# FLC100_remote_HV_v1.net
KiCad netlist of a schematic drawn in EAGLE
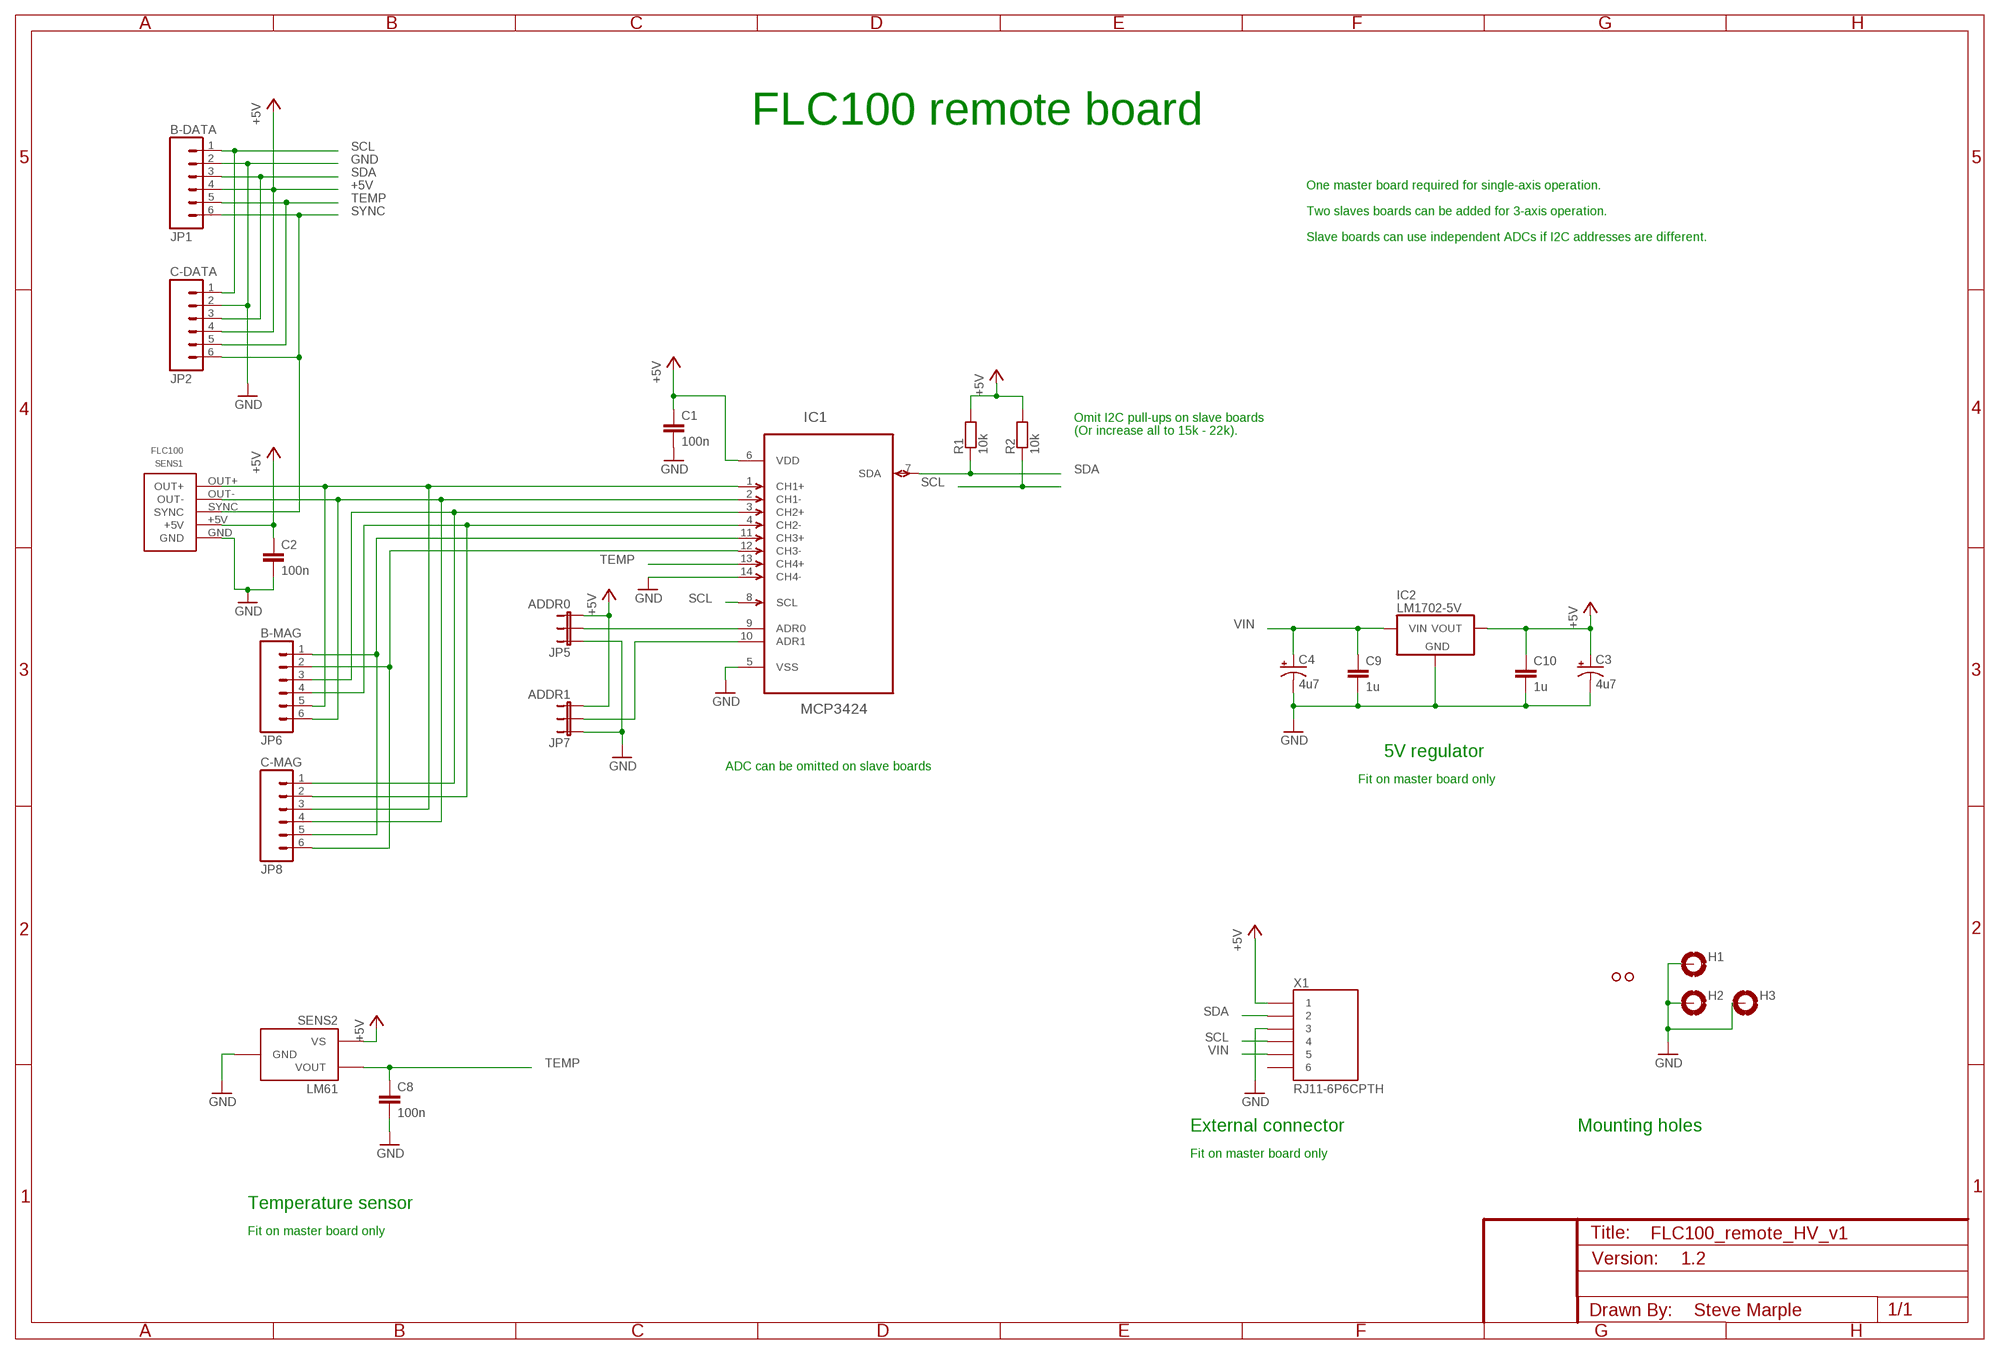
[diagram p0: schematic, sheet 1]

(export (version "E")
  (design (tool "Eeschema 10.0.6"))
  (components
    (comp (ref "C1")
      (value "100n")
      (footprint "eagle-import:CAP-PTH-SMALL")
      (libsource (lib "eagle-import") (part "CAPPTH"))
    )
    (comp (ref "C2")
      (value "100n")
      (footprint "eagle-import:CAP-PTH-SMALL")
      (libsource (lib "eagle-import") (part "CAPPTH"))
    )
    (comp (ref "C3")
      (value "4u7")
      (footprint "eagle-import:CPOL-RADIAL-10UF-25V")
      (libsource (lib "eagle-import") (part "CAP_POLPTH2"))
    )
    (comp (ref "C4")
      (value "4u7")
      (footprint "eagle-import:CPOL-RADIAL-10UF-25V")
      (libsource (lib "eagle-import") (part "CAP_POLPTH2"))
    )
    (comp (ref "C8")
      (value "100n")
      (footprint "eagle-import:CAP-PTH-SMALL")
      (libsource (lib "eagle-import") (part "CAPPTH"))
    )
    (comp (ref "C9")
      (value "1u")
      (footprint "eagle-import:CAP-PTH-5MM")
      (libsource (lib "eagle-import") (part "CAPPTH1"))
    )
    (comp (ref "C10")
      (value "1u")
      (footprint "eagle-import:CAP-PTH-5MM")
      (libsource (lib "eagle-import") (part "CAPPTH1"))
    )
    (comp (ref "H1")
      (value "MOUNT-PAD-ROUND3.0")
      (footprint "eagle-import:3,0-PAD")
      (libsource (lib "eagle-import") (part "MOUNT-PAD-ROUND3.0"))
    )
    (comp (ref "H2")
      (value "MOUNT-PAD-ROUND3.0")
      (footprint "eagle-import:3,0-PAD")
      (libsource (lib "eagle-import") (part "MOUNT-PAD-ROUND3.0"))
    )
    (comp (ref "H3")
      (value "MOUNT-PAD-ROUND3.0")
      (footprint "eagle-import:3,0-PAD")
      (libsource (lib "eagle-import") (part "MOUNT-PAD-ROUND3.0"))
    )
    (comp (ref "IC1")
      (value "MCP3424")
      (footprint "eagle-import:SO14-HAND")
      (libsource (lib "eagle-import") (part "MCP3424-E/SLSO14-HAND"))
    )
    (comp (ref "IC2")
      (value "LM1702-5V")
      (footprint "eagle-import:TO-92@2")
      (libsource (lib "eagle-import") (part "LM1702"))
    )
    (comp (ref "JP1")
      (value "B-DATA")
      (footprint "eagle-import:1X06_FEMALE")
      (libsource (lib "eagle-import") (part "M06FEMALE"))
    )
    (comp (ref "JP2")
      (value "C-DATA")
      (footprint "eagle-import:1X06_FEMALE")
      (libsource (lib "eagle-import") (part "M06FEMALE"))
    )
    (comp (ref "JP5")
      (value "ADDR0")
      (footprint "eagle-import:1X03")
      (libsource (lib "eagle-import") (part "JUMPER-3PTH"))
    )
    (comp (ref "JP6")
      (value "B-MAG")
      (footprint "eagle-import:1X06_FEMALE")
      (libsource (lib "eagle-import") (part "M06FEMALE"))
    )
    (comp (ref "JP7")
      (value "ADDR1")
      (footprint "eagle-import:1X03")
      (libsource (lib "eagle-import") (part "JUMPER-3PTH"))
    )
    (comp (ref "JP8")
      (value "C-MAG")
      (footprint "eagle-import:1X06_FEMALE")
      (libsource (lib "eagle-import") (part "M06FEMALE"))
    )
    (comp (ref "R1")
      (value "10k")
      (footprint "eagle-import:RES-AXIAL-0.4")
      (libsource (lib "eagle-import") (part "RESISTOR"))
    )
    (comp (ref "R2")
      (value "10k")
      (footprint "eagle-import:RES-AXIAL-0.4")
      (libsource (lib "eagle-import") (part "RESISTOR"))
    )
    (comp (ref "SENS1")
      (value "FLC100")
      (footprint "eagle-import:FLC100")
      (libsource (lib "eagle-import") (part "FLC100"))
    )
    (comp (ref "SENS2")
      (value "LM61")
      (footprint "eagle-import:TO-92")
      (libsource (lib "eagle-import") (part "LM61"))
    )
    (comp (ref "U$1")
      (value "PAD")
      (footprint "eagle-import:PAD")
      (libsource (lib "eagle-import") (part "PAD"))
    )
    (comp (ref "U$2")
      (value "PAD")
      (footprint "eagle-import:PAD")
      (libsource (lib "eagle-import") (part "PAD"))
    )
    (comp (ref "X1")
      (value "RJ11-6P6CPTH")
      (footprint "eagle-import:RJ11-6P6C")
      (libsource (lib "eagle-import") (part "RJ11-6P6CPTH"))
    )
  )
  (nets
    (net (code "1") (name "+5V") (class "Default")
      (node (ref "C1") (pin "1") (pinfunction "1_1") (pintype "passive"))
      (node (ref "C10") (pin "1") (pinfunction "1_1") (pintype "passive"))
      (node (ref "C2") (pin "1") (pinfunction "1_1") (pintype "passive"))
      (node (ref "C3") (pin "1") (pinfunction "+_1") (pintype "passive"))
      (node (ref "IC1") (pin "6") (pinfunction "VDD_6") (pintype "power_in"))
      (node (ref "IC2") (pin "3") (pinfunction "VOUT_3") (pintype "passive"))
      (node (ref "JP1") (pin "4") (pinfunction "4_4") (pintype "passive"))
      (node (ref "JP2") (pin "4") (pinfunction "4_4") (pintype "passive"))
      (node (ref "JP5") (pin "3") (pinfunction "3_3") (pintype "passive"))
      (node (ref "JP7") (pin "3") (pinfunction "3_3") (pintype "passive"))
      (node (ref "R1") (pin "P$2") (pinfunction "2_P$2") (pintype "passive"))
      (node (ref "R2") (pin "P$2") (pinfunction "2_P$2") (pintype "passive"))
      (node (ref "SENS1") (pin "+5V") (pinfunction "+5V_+5V") (pintype "power_in"))
      (node (ref "SENS2") (pin "1") (pinfunction "VS_1") (pintype "bidirectional"))
      (node (ref "X1") (pin "1") (pinfunction "1_1") (pintype "bidirectional"))
    )
    (net (code "2") (name "/SCL") (class "Default")
      (node (ref "IC1") (pin "8") (pinfunction "SCL_8") (pintype "input"))
      (node (ref "JP1") (pin "1") (pinfunction "1_1") (pintype "passive"))
      (node (ref "JP2") (pin "1") (pinfunction "1_1") (pintype "passive"))
      (node (ref "R2") (pin "P$1") (pinfunction "1_P$1") (pintype "passive"))
      (node (ref "X1") (pin "4") (pinfunction "4_4") (pintype "bidirectional"))
    )
    (net (code "3") (name "/SDA") (class "Default")
      (node (ref "IC1") (pin "7") (pinfunction "SDA_7") (pintype "bidirectional"))
      (node (ref "JP1") (pin "3") (pinfunction "3_3") (pintype "passive"))
      (node (ref "JP2") (pin "3") (pinfunction "3_3") (pintype "passive"))
      (node (ref "R1") (pin "P$1") (pinfunction "1_P$1") (pintype "passive"))
      (node (ref "X1") (pin "2") (pinfunction "2_2") (pintype "bidirectional"))
    )
    (net (code "4") (name "/SYNC") (class "Default")
      (node (ref "JP1") (pin "6") (pinfunction "6_6") (pintype "passive"))
      (node (ref "JP2") (pin "6") (pinfunction "6_6") (pintype "passive"))
      (node (ref "SENS1") (pin "SYNC") (pinfunction "SYNC_SYNC") (pintype "bidirectional"))
    )
    (net (code "5") (name "/TEMP") (class "Default")
      (node (ref "C8") (pin "1") (pinfunction "1_1") (pintype "passive"))
      (node (ref "IC1") (pin "13") (pinfunction "CH4+_13") (pintype "input"))
      (node (ref "JP1") (pin "5") (pinfunction "5_5") (pintype "passive"))
      (node (ref "JP2") (pin "5") (pinfunction "5_5") (pintype "passive"))
      (node (ref "SENS2") (pin "2") (pinfunction "VOUT_2") (pintype "bidirectional"))
    )
    (net (code "6") (name "/VIN") (class "Default")
      (node (ref "C4") (pin "1") (pinfunction "+_1") (pintype "passive"))
      (node (ref "C9") (pin "1") (pinfunction "1_1") (pintype "passive"))
      (node (ref "IC2") (pin "2") (pinfunction "VIN_2") (pintype "input"))
      (node (ref "X1") (pin "5") (pinfunction "5_5") (pintype "bidirectional"))
    )
    (net (code "7") (name "GND") (class "Default")
      (node (ref "C1") (pin "2") (pinfunction "2_2") (pintype "passive"))
      (node (ref "C10") (pin "2") (pinfunction "2_2") (pintype "passive"))
      (node (ref "C2") (pin "2") (pinfunction "2_2") (pintype "passive"))
      (node (ref "C3") (pin "2") (pinfunction "-_2") (pintype "passive"))
      (node (ref "C4") (pin "2") (pinfunction "-_2") (pintype "passive"))
      (node (ref "C8") (pin "2") (pinfunction "2_2") (pintype "passive"))
      (node (ref "C9") (pin "2") (pinfunction "2_2") (pintype "passive"))
      (node (ref "H1") (pin "B3,0") (pinfunction "MOUNT_B3,0") (pintype "passive"))
      (node (ref "H2") (pin "B3,0") (pinfunction "MOUNT_B3,0") (pintype "passive"))
      (node (ref "H3") (pin "B3,0") (pinfunction "MOUNT_B3,0") (pintype "passive"))
      (node (ref "IC1") (pin "14") (pinfunction "CH4-_14") (pintype "input"))
      (node (ref "IC1") (pin "5") (pinfunction "VSS_5") (pintype "power_in"))
      (node (ref "IC2") (pin "1") (pinfunction "GND_1") (pintype "passive"))
      (node (ref "JP1") (pin "2") (pinfunction "2_2") (pintype "passive"))
      (node (ref "JP2") (pin "2") (pinfunction "2_2") (pintype "passive"))
      (node (ref "JP5") (pin "1") (pinfunction "1_1") (pintype "passive"))
      (node (ref "JP7") (pin "1") (pinfunction "1_1") (pintype "passive"))
      (node (ref "SENS1") (pin "GND") (pinfunction "GND_GND") (pintype "power_in"))
      (node (ref "SENS2") (pin "3") (pinfunction "GND_3") (pintype "bidirectional"))
      (node (ref "X1") (pin "3") (pinfunction "3_3") (pintype "bidirectional"))
    )
    (net (code "8") (name "Net-(IC1-ADR0)") (class "Default")
      (node (ref "IC1") (pin "9") (pinfunction "ADR0_9") (pintype "input"))
      (node (ref "JP5") (pin "2") (pinfunction "2_2") (pintype "passive"))
    )
    (net (code "9") (name "Net-(IC1-ADR1)") (class "Default")
      (node (ref "IC1") (pin "10") (pinfunction "ADR1_10") (pintype "input"))
      (node (ref "JP7") (pin "2") (pinfunction "2_2") (pintype "passive"))
    )
    (net (code "10") (name "Net-(IC1-CH1+)") (class "Default")
      (node (ref "IC1") (pin "1") (pinfunction "CH1+_1") (pintype "input"))
      (node (ref "JP6") (pin "5") (pinfunction "5_5") (pintype "passive"))
      (node (ref "JP8") (pin "3") (pinfunction "3_3") (pintype "passive"))
      (node (ref "SENS1") (pin "OUT+") (pinfunction "OUT+_OUT+") (pintype "output"))
    )
    (net (code "11") (name "Net-(IC1-CH1-)") (class "Default")
      (node (ref "IC1") (pin "2") (pinfunction "CH1-_2") (pintype "input"))
      (node (ref "JP6") (pin "6") (pinfunction "6_6") (pintype "passive"))
      (node (ref "JP8") (pin "4") (pinfunction "4_4") (pintype "passive"))
      (node (ref "SENS1") (pin "OUT-") (pinfunction "OUT-_OUT-") (pintype "output"))
    )
    (net (code "12") (name "Net-(IC1-CH2+)") (class "Default")
      (node (ref "IC1") (pin "3") (pinfunction "CH2+_3") (pintype "input"))
      (node (ref "JP6") (pin "3") (pinfunction "3_3") (pintype "passive"))
      (node (ref "JP8") (pin "1") (pinfunction "1_1") (pintype "passive"))
    )
    (net (code "13") (name "Net-(IC1-CH2-)") (class "Default")
      (node (ref "IC1") (pin "4") (pinfunction "CH2-_4") (pintype "input"))
      (node (ref "JP6") (pin "4") (pinfunction "4_4") (pintype "passive"))
      (node (ref "JP8") (pin "2") (pinfunction "2_2") (pintype "passive"))
    )
    (net (code "14") (name "Net-(IC1-CH3+)") (class "Default")
      (node (ref "IC1") (pin "11") (pinfunction "CH3+_11") (pintype "input"))
      (node (ref "JP6") (pin "1") (pinfunction "1_1") (pintype "passive"))
      (node (ref "JP8") (pin "5") (pinfunction "5_5") (pintype "passive"))
    )
    (net (code "15") (name "Net-(IC1-CH3-)") (class "Default")
      (node (ref "IC1") (pin "12") (pinfunction "CH3-_12") (pintype "input"))
      (node (ref "JP6") (pin "2") (pinfunction "2_2") (pintype "passive"))
      (node (ref "JP8") (pin "6") (pinfunction "6_6") (pintype "passive"))
    )
    (net (code "16") (name "unconnected-(U$1-Pad1)") (class "Default")
      (node (ref "U$1") (pin "1") (pinfunction "1_1") (pintype "bidirectional"))
    )
    (net (code "17") (name "unconnected-(U$2-Pad1)") (class "Default")
      (node (ref "U$2") (pin "1") (pinfunction "1_1") (pintype "bidirectional"))
    )
    (net (code "18") (name "unconnected-(X1-Pad6)") (class "Default")
      (node (ref "X1") (pin "6") (pinfunction "6_6") (pintype "bidirectional"))
    )
  )
)
